# Master.net
KiCad netlist of a schematic drawn in Altium Designer
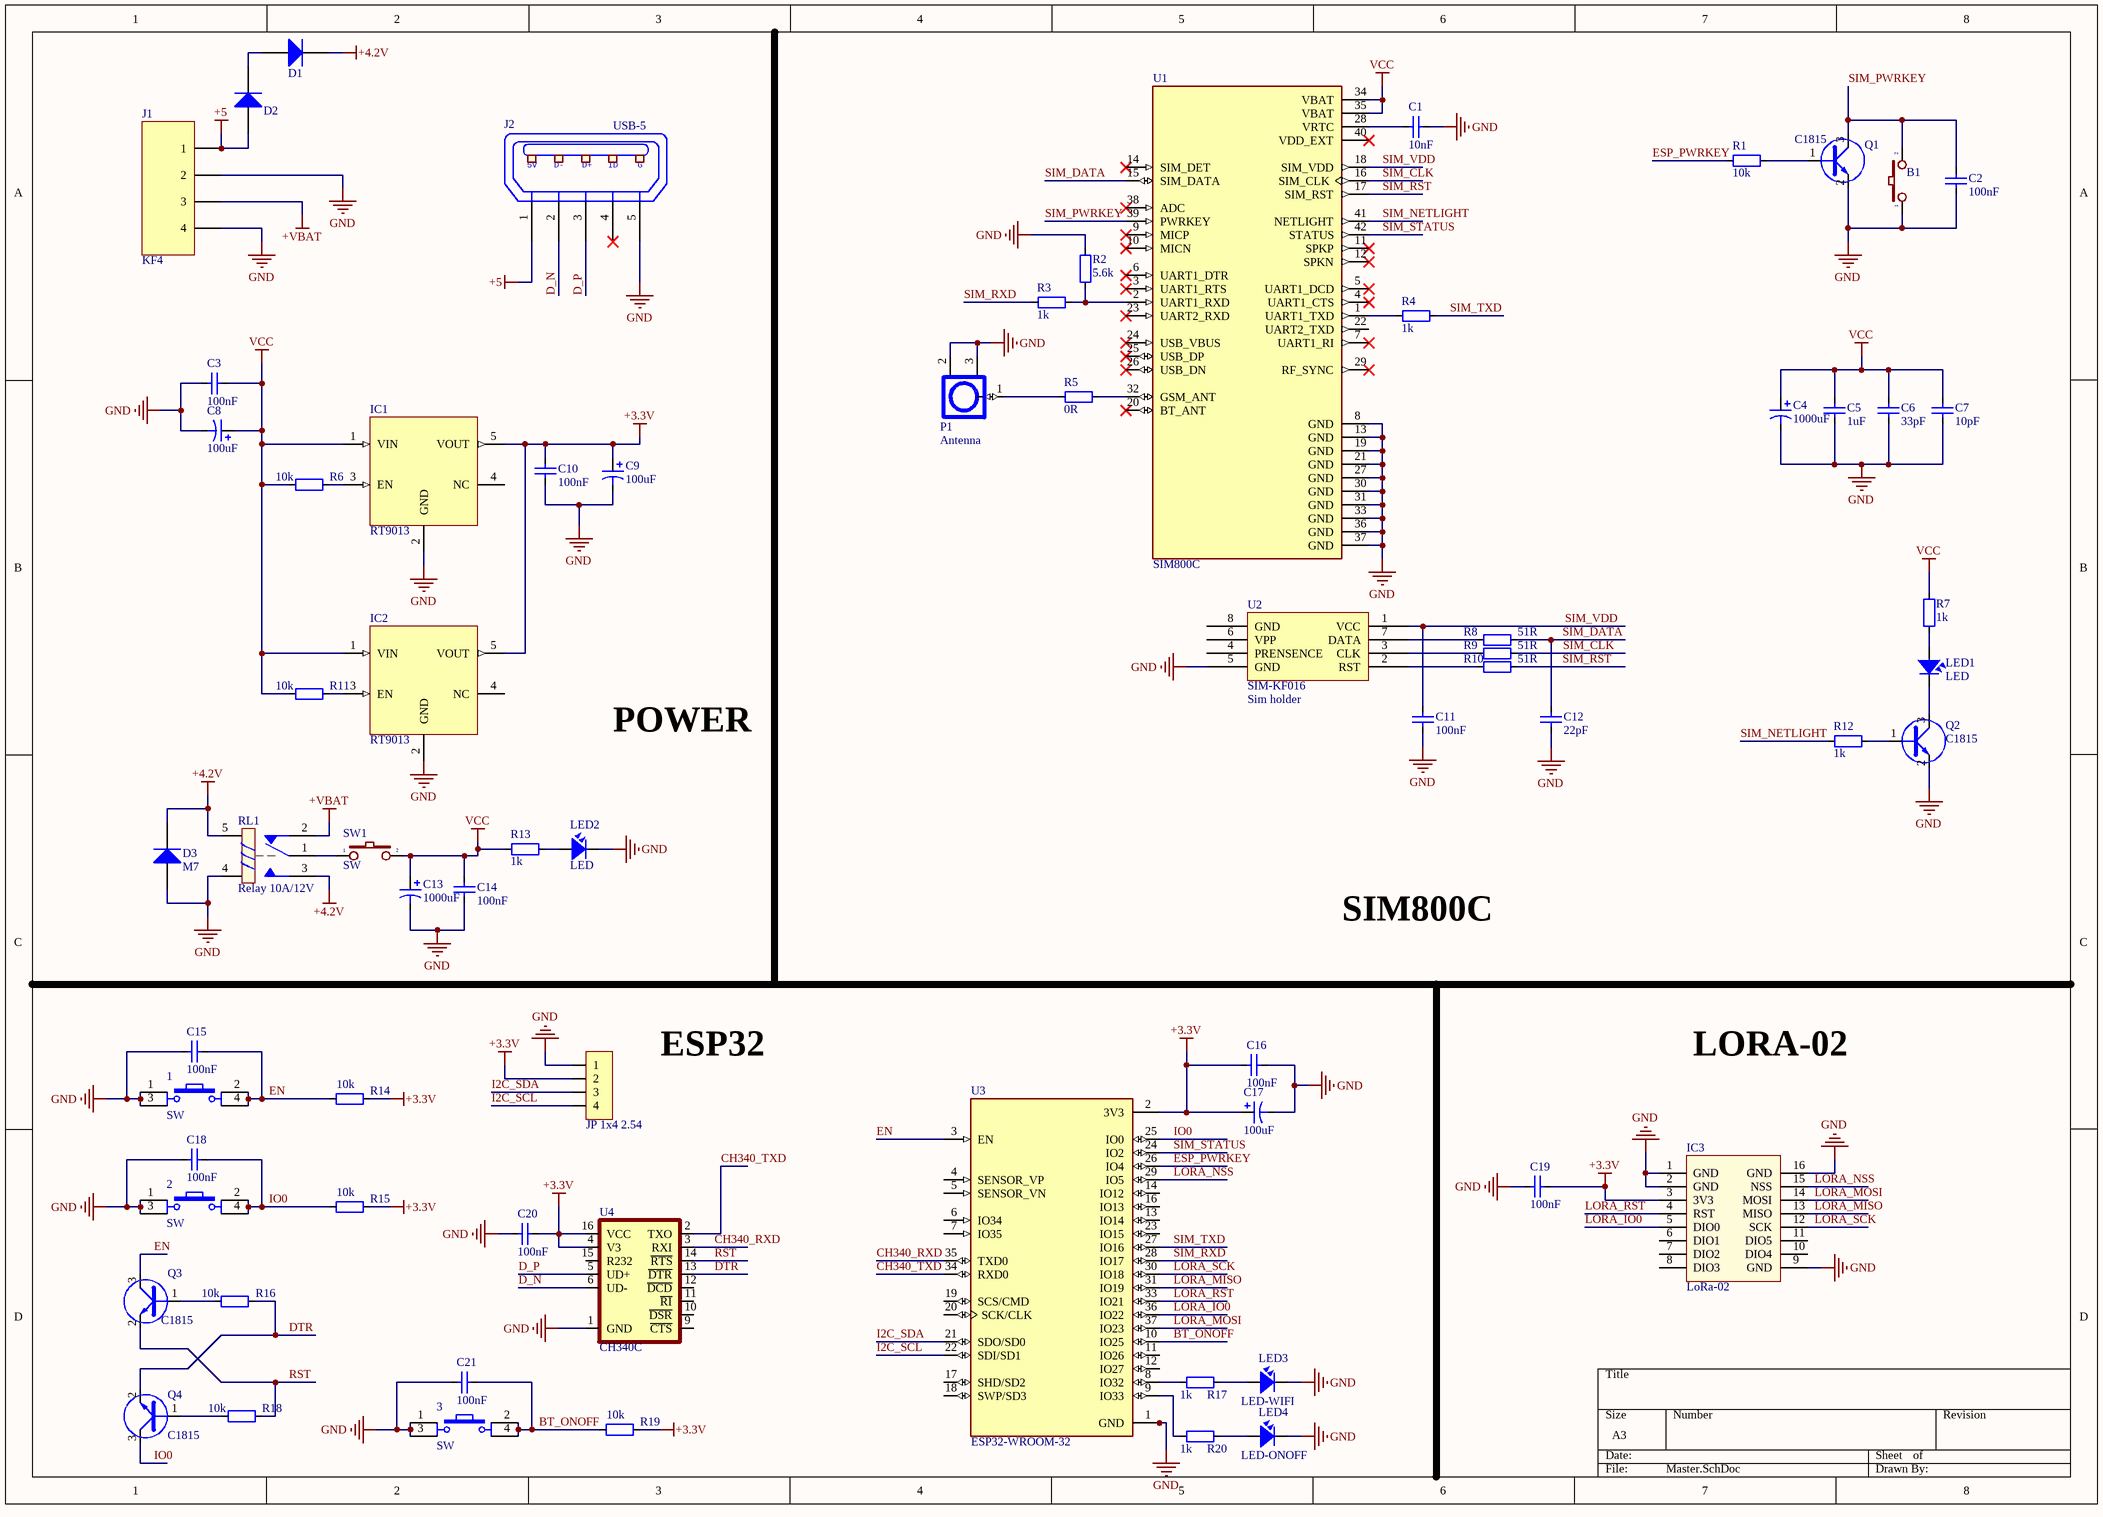
[diagram p0: Master.SchDoc]

(export (version "E")
  (design (tool "Eeschema 10.0.6"))
  (components
    (comp (ref "1")
      (value "SW")
      (footprint "SW4")
      (description "Switch button 4 pin")
      (libsource (lib "My Library") (part "SW4"))
    )
    (comp (ref "2")
      (value "SW")
      (footprint "SW4")
      (description "Switch button 4 pin")
      (libsource (lib "My Library") (part "SW4"))
    )
    (comp (ref "3")
      (value "SW")
      (footprint "SW4")
      (description "Switch button 4 pin")
      (libsource (lib "My Library") (part "SW4"))
    )
    (comp (ref "B1")
      (value "Button 3x4x2.5")
      (footprint "Button 3x4x2.5")
      (libsource (lib "My Library") (part "Button 3x4x2.5"))
    )
    (comp (ref "C1")
      (value "10nF")
      (footprint "CAP_0805")
      (description "Capacitor")
      (fields (field (name "PUBLISHER") "Altium Limited"))
      (libsource (lib "My Library") (part "CapSMD"))
    )
    (comp (ref "C2")
      (value "100nF")
      (footprint "CAP_0805")
      (description "Capacitor")
      (fields (field (name "PUBLISHER") "Altium Limited"))
      (libsource (lib "My Library") (part "CapSMD"))
    )
    (comp (ref "C3")
      (value "100nF")
      (footprint "CAP_0805")
      (description "Capacitor")
      (fields (field (name "PUBLISHER") "Altium Limited"))
      (libsource (lib "My Library") (part "CapSMD"))
    )
    (comp (ref "C4")
      (value "1000uF")
      (footprint "C8mm")
      (description "1000uF 16V 8x16mm")
      (fields (field (name "PUBLISHER") "Altium Limited"))
      (libsource (lib "My Library") (part "Cap Pol"))
    )
    (comp (ref "C5")
      (value "1uF")
      (footprint "CAP_0805")
      (description "Capacitor")
      (fields (field (name "PUBLISHER") "Altium Limited"))
      (libsource (lib "My Library") (part "CapSMD"))
    )
    (comp (ref "C6")
      (value "33pF")
      (footprint "CAP_0805")
      (description "Capacitor")
      (fields (field (name "PUBLISHER") "Altium Limited"))
      (libsource (lib "My Library") (part "CapSMD"))
    )
    (comp (ref "C7")
      (value "10pF")
      (footprint "CAP_0805")
      (description "Capacitor")
      (fields (field (name "PUBLISHER") "Altium Limited"))
      (libsource (lib "My Library") (part "CapSMD"))
    )
    (comp (ref "C8")
      (value "100uF")
      (footprint "C5mm")
      (description "100uF 16V")
      (fields (field (name "PUBLISHER") "Altium Limited"))
      (libsource (lib "My Library") (part "Cap Pol"))
    )
    (comp (ref "C9")
      (value "100uF")
      (footprint "C5mm")
      (description "100uF 16V")
      (fields (field (name "PUBLISHER") "Altium Limited"))
      (libsource (lib "My Library") (part "Cap Pol"))
    )
    (comp (ref "C10")
      (value "100nF")
      (footprint "CAP_0805")
      (description "Capacitor")
      (fields (field (name "PUBLISHER") "Altium Limited"))
      (libsource (lib "My Library") (part "CapSMD"))
    )
    (comp (ref "C11")
      (value "100nF")
      (footprint "CAP_0805")
      (description "Capacitor")
      (fields (field (name "PUBLISHER") "Altium Limited"))
      (libsource (lib "My Library") (part "CapSMD"))
    )
    (comp (ref "C12")
      (value "22pF")
      (footprint "CAP_0805")
      (description "Capacitor")
      (fields (field (name "PUBLISHER") "Altium Limited"))
      (libsource (lib "My Library") (part "CapSMD"))
    )
    (comp (ref "C13")
      (value "1000uF")
      (footprint "C8mm")
      (description "1000uF 16V 8x16mm")
      (fields (field (name "PUBLISHER") "Altium Limited"))
      (libsource (lib "My Library") (part "Cap Pol"))
    )
    (comp (ref "C14")
      (value "100nF")
      (footprint "CAP_0805")
      (description "Capacitor")
      (fields (field (name "PUBLISHER") "Altium Limited"))
      (libsource (lib "My Library") (part "CapSMD"))
    )
    (comp (ref "C15")
      (value "100nF")
      (footprint "CAP_0805")
      (description "Capacitor")
      (fields (field (name "PUBLISHER") "Altium Limited"))
      (libsource (lib "My Library") (part "CapSMD"))
    )
    (comp (ref "C16")
      (value "100nF")
      (footprint "CAP_0805")
      (description "Capacitor")
      (fields (field (name "PUBLISHER") "Altium Limited"))
      (libsource (lib "My Library") (part "CapSMD"))
    )
    (comp (ref "C17")
      (value "100uF")
      (footprint "C5mm")
      (description "100uF 16V")
      (fields (field (name "PUBLISHER") "Altium Limited"))
      (libsource (lib "My Library") (part "Cap Pol"))
    )
    (comp (ref "C18")
      (value "100nF")
      (footprint "CAP_0805")
      (description "Capacitor")
      (fields (field (name "PUBLISHER") "Altium Limited"))
      (libsource (lib "My Library") (part "CapSMD"))
    )
    (comp (ref "C19")
      (value "100nF")
      (footprint "CAP_0805")
      (description "Capacitor")
      (fields (field (name "PUBLISHER") "Altium Limited"))
      (libsource (lib "My Library") (part "CapSMD"))
    )
    (comp (ref "C20")
      (value "100nF")
      (footprint "CAP_0805")
      (description "Capacitor")
      (fields (field (name "PUBLISHER") "Altium Limited"))
      (libsource (lib "My Library") (part "CapSMD"))
    )
    (comp (ref "C21")
      (value "100nF")
      (footprint "CAP_0805")
      (description "Capacitor")
      (fields (field (name "PUBLISHER") "Altium Limited"))
      (libsource (lib "My Library") (part "CapSMD"))
    )
    (comp (ref "D1")
      (value "SS34 Diode 3A 40V")
      (footprint "DIODE SMA")
      (description "Dán")
      (libsource (lib "Altium_Lib_by_KhueNguyenCreator") (part "Diode M7 ( 4007 )"))
    )
    (comp (ref "D2")
      (value "SS34 Diode 3A 40V")
      (footprint "DIODE SMA")
      (description "Dán")
      (libsource (lib "Altium_Lib_by_KhueNguyenCreator") (part "Diode M7 ( 4007 )"))
    )
    (comp (ref "D3")
      (value "M7")
      (footprint "DIODE SMA")
      (description "Dán")
      (libsource (lib "Altium_Lib_by_KhueNguyenCreator") (part "Diode M7 ( 4007 )"))
    )
    (comp (ref "IC1")
      (value "RT9013")
      (footprint "SOT23-5")
      (description "RT9013-33GB IC REG LINEAR 3.3V 500mA SOT23-5")
      (libsource (lib "My Library") (part "RT9013"))
    )
    (comp (ref "IC2")
      (value "RT9013")
      (footprint "SOT23-5")
      (description "RT9013-33GB IC REG LINEAR 3.3V 500mA SOT23-5")
      (libsource (lib "My Library") (part "RT9013"))
    )
    (comp (ref "IC3") (value "LoRa-02") (footprint "LoRa-02") (libsource (lib "My Library") (part "LoRa-02")))
    (comp (ref "J1")
      (value "KF4")
      (footprint "KF4-5.08")
      (fields
        (field (name "MANUFACTURER") "Würth Elektronik eiSos GmbH")
        (field (name "PARTNO") "691133710004")
        (field (name "CREATED BY") "Baojun Chen")
      )
      (libsource (lib "My Library") (part "KF4"))
    )
    (comp (ref "J2")
      (value "USB-5")
      (footprint "USB-M1")
      (fields
        (field (name "MANUFACTURER") "FCI")
        (field (name "MANUFACTURER PART NUMBER") "10118193-0001LF")
        (field (name ".CREATOR") "MM")
        (field (name ".CHECKED PCB") "RF")
        (field (name ".CHECKED SCH") "MM")
      )
      (libsource (lib "My Library") (part "USB-5"))
    )
    (comp (ref "JP1")
      (value "JP 1x4 2.54")
      (footprint "JP 1x4 DT")
      (description "Cắm")
      (libsource (lib "Altium_Lib_by_KhueNguyenCreator") (part "JP 1x4 2.54 Duc Thang"))
    )
    (comp (ref "LED1")
      (value "LED")
      (footprint "LED-0805-Red")
      (description "LED Single colour Green and Red")
      (libsource (lib "My Library") (part "LED"))
    )
    (comp (ref "LED2")
      (value "LED")
      (footprint "LED-0805-Red")
      (description "LED Single colour Green and Red")
      (libsource (lib "My Library") (part "LED"))
    )
    (comp (ref "LED3")
      (value "LED-WIFI")
      (footprint "LED-0805-Red")
      (description "LED Single colour Green and Red")
      (libsource (lib "My Library") (part "LED"))
    )
    (comp (ref "LED4")
      (value "LED-ONOFF")
      (footprint "LED-0805-Red")
      (description "LED Single colour Green and Red")
      (libsource (lib "My Library") (part "LED"))
    )
    (comp (ref "P1")
      (value "Antenna")
      (footprint "IPXS")
      (description "Antenna GSM GPS")
      (libsource (lib "My Library") (part "IPXSx66"))
    )
    (comp (ref "Q1")
      (value "C1815")
      (footprint "SOT23D")
      (description "NPN 600mW, ECB")
      (libsource (lib "My Library") (part "2SC1815"))
    )
    (comp (ref "Q2")
      (value "C1815")
      (footprint "SOT23D")
      (description "NPN 600mW, ECB")
      (libsource (lib "My Library") (part "2SC1815"))
    )
    (comp (ref "Q3")
      (value "C1815")
      (footprint "SOT23D")
      (description "NPN 600mW, ECB")
      (libsource (lib "") (part "2SC1815_1"))
    )
    (comp (ref "Q4")
      (value "C1815")
      (footprint "SOT23D")
      (description "NPN 600mW, ECB")
      (libsource (lib "My Library") (part "2SC1815"))
    )
    (comp (ref "R1")
      (value "10k")
      (footprint "RES-SMD-0805")
      (description "Resistor")
      (fields
        (field (name "MANUFACTURER") "Generic Components")
        (field (name "PUBLISHER") "Altium Hobart Technology Centre")
      )
      (libsource (lib "My Library") (part "Resistor - SMD"))
    )
    (comp (ref "R2")
      (value "5.6k")
      (footprint "RES-SMD-0805")
      (description "Resistor")
      (fields
        (field (name "MANUFACTURER") "Generic Components")
        (field (name "PUBLISHER") "Altium Hobart Technology Centre")
      )
      (libsource (lib "My Library") (part "Resistor - SMD"))
    )
    (comp (ref "R3")
      (value "1k")
      (footprint "RES-SMD-0805")
      (description "Resistor")
      (fields
        (field (name "MANUFACTURER") "Generic Components")
        (field (name "PUBLISHER") "Altium Hobart Technology Centre")
      )
      (libsource (lib "My Library") (part "Resistor - SMD"))
    )
    (comp (ref "R4")
      (value "1k")
      (footprint "RES-SMD-0805")
      (description "Resistor")
      (fields
        (field (name "MANUFACTURER") "Generic Components")
        (field (name "PUBLISHER") "Altium Hobart Technology Centre")
      )
      (libsource (lib "My Library") (part "Resistor - SMD"))
    )
    (comp (ref "R5")
      (value "0R")
      (footprint "RES-SMD-0805")
      (description "Resistor")
      (fields
        (field (name "MANUFACTURER") "Generic Components")
        (field (name "PUBLISHER") "Altium Hobart Technology Centre")
      )
      (libsource (lib "My Library") (part "Resistor - SMD"))
    )
    (comp (ref "R6")
      (value "10k")
      (footprint "RES-SMD-0805")
      (description "Resistor")
      (fields
        (field (name "MANUFACTURER") "Generic Components")
        (field (name "PUBLISHER") "Altium Hobart Technology Centre")
      )
      (libsource (lib "My Library") (part "Resistor - SMD"))
    )
    (comp (ref "R7")
      (value "1k")
      (footprint "RES-SMD-0805")
      (description "Resistor")
      (fields
        (field (name "MANUFACTURER") "Generic Components")
        (field (name "PUBLISHER") "Altium Hobart Technology Centre")
      )
      (libsource (lib "My Library") (part "Resistor - SMD"))
    )
    (comp (ref "R8")
      (value "51R")
      (footprint "RES-SMD-0805")
      (description "Resistor")
      (fields
        (field (name "MANUFACTURER") "Generic Components")
        (field (name "PUBLISHER") "Altium Hobart Technology Centre")
      )
      (libsource (lib "My Library") (part "Resistor - SMD"))
    )
    (comp (ref "R9")
      (value "51R")
      (footprint "RES-SMD-0805")
      (description "Resistor")
      (fields
        (field (name "MANUFACTURER") "Generic Components")
        (field (name "PUBLISHER") "Altium Hobart Technology Centre")
      )
      (libsource (lib "My Library") (part "Resistor - SMD"))
    )
    (comp (ref "R10")
      (value "51R")
      (footprint "RES-SMD-0805")
      (description "Resistor")
      (fields
        (field (name "MANUFACTURER") "Generic Components")
        (field (name "PUBLISHER") "Altium Hobart Technology Centre")
      )
      (libsource (lib "My Library") (part "Resistor - SMD"))
    )
    (comp (ref "R11")
      (value "10k")
      (footprint "RES-SMD-0805")
      (description "Resistor")
      (fields
        (field (name "MANUFACTURER") "Generic Components")
        (field (name "PUBLISHER") "Altium Hobart Technology Centre")
      )
      (libsource (lib "My Library") (part "Resistor - SMD"))
    )
    (comp (ref "R12")
      (value "1k")
      (footprint "RES-SMD-0805")
      (description "Resistor")
      (fields
        (field (name "MANUFACTURER") "Generic Components")
        (field (name "PUBLISHER") "Altium Hobart Technology Centre")
      )
      (libsource (lib "My Library") (part "Resistor - SMD"))
    )
    (comp (ref "R13")
      (value "1k")
      (footprint "RES-SMD-0805")
      (description "Resistor")
      (fields
        (field (name "MANUFACTURER") "Generic Components")
        (field (name "PUBLISHER") "Altium Hobart Technology Centre")
      )
      (libsource (lib "My Library") (part "Resistor - SMD"))
    )
    (comp (ref "R14")
      (value "10k")
      (footprint "RES-SMD-0805")
      (description "Resistor")
      (fields
        (field (name "MANUFACTURER") "Generic Components")
        (field (name "PUBLISHER") "Altium Hobart Technology Centre")
      )
      (libsource (lib "My Library") (part "Resistor - SMD"))
    )
    (comp (ref "R15")
      (value "10k")
      (footprint "RES-SMD-0805")
      (description "Resistor")
      (fields
        (field (name "MANUFACTURER") "Generic Components")
        (field (name "PUBLISHER") "Altium Hobart Technology Centre")
      )
      (libsource (lib "My Library") (part "Resistor - SMD"))
    )
    (comp (ref "R16")
      (value "10k")
      (footprint "RES-SMD-0805")
      (description "Resistor")
      (fields
        (field (name "MANUFACTURER") "Generic Components")
        (field (name "PUBLISHER") "Altium Hobart Technology Centre")
      )
      (libsource (lib "My Library") (part "Resistor - SMD"))
    )
    (comp (ref "R17")
      (value "1k")
      (footprint "RES-SMD-0805")
      (description "Resistor")
      (fields
        (field (name "MANUFACTURER") "Generic Components")
        (field (name "PUBLISHER") "Altium Hobart Technology Centre")
      )
      (libsource (lib "My Library") (part "Resistor - SMD"))
    )
    (comp (ref "R18")
      (value "10k")
      (footprint "RES-SMD-0805")
      (description "Resistor")
      (fields
        (field (name "MANUFACTURER") "Generic Components")
        (field (name "PUBLISHER") "Altium Hobart Technology Centre")
      )
      (libsource (lib "My Library") (part "Resistor - SMD"))
    )
    (comp (ref "R19")
      (value "10k")
      (footprint "RES-SMD-0805")
      (description "Resistor")
      (fields
        (field (name "MANUFACTURER") "Generic Components")
        (field (name "PUBLISHER") "Altium Hobart Technology Centre")
      )
      (libsource (lib "My Library") (part "Resistor - SMD"))
    )
    (comp (ref "R20")
      (value "1k")
      (footprint "RES-SMD-0805")
      (description "Resistor")
      (fields
        (field (name "MANUFACTURER") "Generic Components")
        (field (name "PUBLISHER") "Altium Hobart Technology Centre")
      )
      (libsource (lib "My Library") (part "Resistor - SMD"))
    )
    (comp (ref "RL1")
      (value "Relay 10A/12V")
      (footprint "RELAY 5")
      (description "Relay SPDT,10A - 12VDC 5 Pin")
      (libsource (lib "My Library") (part "Relay 5"))
    )
    (comp (ref "SW1")
      (value "SW")
      (footprint "SW2")
      (description "Switch button 2 pin")
      (libsource (lib "My Library") (part "SW2"))
    )
    (comp (ref "U1") (value "SIM800C") (footprint "SIM800C") (libsource (lib "My Library") (part "SIM800C")))
    (comp (ref "U2")
      (value "SIM-KF016")
      (footprint "Sim Socket")
      (description "SIM Card Holder KF-016")
      (fields (field (name "ALTIUM_VALUE") "Sim holder"))
      (libsource (lib "My Library") (part "Sim holder"))
    )
    (comp (ref "U3")
      (value "ESP32-WROOM-32")
      (footprint "MODULE_ESP32-WROOM-32")
      (description "Bluetooth, WiFi Transceiver Module 2.4GHz ~ 2.5GHz Surface Mount")
      (fields (field (name "MF") "Espressif Systems") (field (name "DIGI-KEY_PART_NUMBER") "1904-1010-1-ND"))
      (libsource (lib "My Library") (part "ESP32-WROOM-32"))
    )
    (comp (ref "U4")
      (value "CH340C")
      (footprint "SO016")
      (description "USB to serial chip CH340")
      (fields (field (name "MF") "WCH"))
      (libsource (lib "My Library") (part "CH340C"))
    )
  )
  (nets
    (net (code "1") (name "+3.3V") (class "Default")
      (node (ref "C10") (pin "1") (pinfunction "1_1") (pintype "passive"))
      (node (ref "C16") (pin "1") (pinfunction "1_1") (pintype "passive"))
      (node (ref "C17") (pin "1") (pinfunction "1_1") (pintype "passive"))
      (node (ref "C19") (pin "1") (pinfunction "1_1") (pintype "passive"))
      (node (ref "C20") (pin "2") (pinfunction "2_2") (pintype "passive"))
      (node (ref "C9") (pin "1") (pinfunction "1_1") (pintype "passive"))
      (node (ref "IC1") (pin "5") (pinfunction "VOUT_5") (pintype "output"))
      (node (ref "IC2") (pin "5") (pinfunction "VOUT_5") (pintype "output"))
      (node (ref "IC3") (pin "3") (pinfunction "3V3_3") (pintype "passive"))
      (node (ref "JP1") (pin "2") (pinfunction "2_2") (pintype "passive"))
      (node (ref "R14") (pin "1") (pinfunction "1_1") (pintype "passive"))
      (node (ref "R15") (pin "1") (pinfunction "1_1") (pintype "passive"))
      (node (ref "R19") (pin "1") (pinfunction "1_1") (pintype "passive"))
      (node (ref "U3") (pin "2") (pinfunction "3V3_2") (pintype "power_in"))
      (node (ref "U4") (pin "16") (pinfunction "VCC_16") (pintype "bidirectional"))
      (node (ref "U4") (pin "4") (pinfunction "V3_4") (pintype "bidirectional"))
    )
    (net (code "2") (name "+4.2V") (class "Default")
      (node (ref "D1") (pin "2") (pinfunction "K_2") (pintype "passive"))
      (node (ref "D3") (pin "2") (pinfunction "K_2") (pintype "passive"))
      (node (ref "RL1") (pin "3") (pinfunction "3_3") (pintype "passive"))
      (node (ref "RL1") (pin "5") (pinfunction "5_5") (pintype "passive"))
    )
    (net (code "3") (name "+5") (class "Default")
      (node (ref "D2") (pin "1") (pinfunction "A_1") (pintype "passive"))
      (node (ref "J1") (pin "1") (pinfunction "1_1") (pintype "passive"))
      (node (ref "J2") (pin "1") (pinfunction "P1_1") (pintype "passive"))
    )
    (net (code "4") (name "+VBAT") (class "Default")
      (node (ref "J1") (pin "3") (pinfunction "3_3") (pintype "passive"))
      (node (ref "RL1") (pin "2") (pinfunction "2_2") (pintype "passive"))
    )
    (net (code "6") (name "/BT_ONOFF") (class "Default")
      (node (ref "3") (pin "2") (pintype "passive"))
      (node (ref "3") (pin "4") (pintype "passive"))
      (node (ref "C21") (pin "2") (pinfunction "2_2") (pintype "passive"))
      (node (ref "R19") (pin "2") (pinfunction "2_2") (pintype "passive"))
      (node (ref "U3") (pin "10") (pinfunction "IO25_10") (pintype "bidirectional"))
    )
    (net (code "7") (name "/CH340_RXD") (class "Default")
      (node (ref "U3") (pin "35") (pinfunction "TXD0_35") (pintype "bidirectional"))
      (node (ref "U4") (pin "3") (pinfunction "RXI_3") (pintype "bidirectional"))
    )
    (net (code "8") (name "/CH340_TXD") (class "Default")
      (node (ref "U3") (pin "34") (pinfunction "RXD0_34") (pintype "bidirectional"))
      (node (ref "U4") (pin "2") (pinfunction "TXO_2") (pintype "bidirectional"))
    )
    (net (code "9") (name "/DTR") (class "Default")
      (node (ref "Q4") (pin "2") (pinfunction "E_2") (pintype "passive"))
      (node (ref "R16") (pin "1") (pinfunction "1_1") (pintype "passive"))
      (node (ref "U4") (pin "13") (pinfunction "~{DTR}_13") (pintype "bidirectional"))
    )
    (net (code "10") (name "/D_N") (class "Default")
      (node (ref "J2") (pin "2") (pinfunction "P2_2") (pintype "passive"))
      (node (ref "U4") (pin "6") (pinfunction "UD-_6") (pintype "bidirectional"))
    )
    (net (code "11") (name "/D_P") (class "Default")
      (node (ref "J2") (pin "3") (pinfunction "P3_3") (pintype "passive"))
      (node (ref "U4") (pin "5") (pinfunction "UD+_5") (pintype "bidirectional"))
    )
    (net (code "12") (name "/EN") (class "Default")
      (node (ref "1") (pin "2") (pintype "passive"))
      (node (ref "1") (pin "4") (pintype "passive"))
      (node (ref "C15") (pin "2") (pinfunction "2_2") (pintype "passive"))
      (node (ref "Q3") (pin "3") (pinfunction "C_3") (pintype "passive"))
      (node (ref "R14") (pin "2") (pinfunction "2_2") (pintype "passive"))
      (node (ref "U3") (pin "3") (pinfunction "EN_3") (pintype "input"))
    )
    (net (code "13") (name "/ESP_PWRKEY") (class "Default")
      (node (ref "R1") (pin "1") (pinfunction "1_1") (pintype "passive"))
      (node (ref "U3") (pin "26") (pinfunction "IO4_26") (pintype "bidirectional"))
    )
    (net (code "14") (name "/I2C_SCL") (class "Default")
      (node (ref "JP1") (pin "4") (pinfunction "4_4") (pintype "passive"))
      (node (ref "U3") (pin "22") (pinfunction "SDI/SD1_22") (pintype "bidirectional"))
    )
    (net (code "15") (name "/I2C_SDA") (class "Default")
      (node (ref "JP1") (pin "3") (pinfunction "3_3") (pintype "passive"))
      (node (ref "U3") (pin "21") (pinfunction "SDO/SD0_21") (pintype "bidirectional"))
    )
    (net (code "16") (name "/IO0") (class "Default")
      (node (ref "2") (pin "2") (pintype "passive"))
      (node (ref "2") (pin "4") (pintype "passive"))
      (node (ref "C18") (pin "2") (pinfunction "2_2") (pintype "passive"))
      (node (ref "Q4") (pin "3") (pinfunction "C_3") (pintype "passive"))
      (node (ref "R15") (pin "2") (pinfunction "2_2") (pintype "passive"))
      (node (ref "U3") (pin "25") (pinfunction "IO0_25") (pintype "bidirectional"))
    )
    (net (code "17") (name "/LORA_IO0") (class "Default")
      (node (ref "IC3") (pin "5") (pinfunction "DIO0_5") (pintype "passive"))
      (node (ref "U3") (pin "36") (pinfunction "IO22_36") (pintype "bidirectional"))
    )
    (net (code "18") (name "/LORA_MISO") (class "Default")
      (node (ref "IC3") (pin "13") (pinfunction "MISO_13") (pintype "passive"))
      (node (ref "U3") (pin "31") (pinfunction "IO19_31") (pintype "bidirectional"))
    )
    (net (code "19") (name "/LORA_MOSI") (class "Default")
      (node (ref "IC3") (pin "14") (pinfunction "MOSI_14") (pintype "passive"))
      (node (ref "U3") (pin "37") (pinfunction "IO23_37") (pintype "bidirectional"))
    )
    (net (code "20") (name "/LORA_NSS") (class "Default")
      (node (ref "IC3") (pin "15") (pinfunction "NSS_15") (pintype "passive"))
      (node (ref "U3") (pin "29") (pinfunction "IO5_29") (pintype "bidirectional"))
    )
    (net (code "21") (name "/LORA_RST") (class "Default")
      (node (ref "IC3") (pin "4") (pinfunction "RST_4") (pintype "passive"))
      (node (ref "U3") (pin "33") (pinfunction "IO21_33") (pintype "bidirectional"))
    )
    (net (code "22") (name "/LORA_SCK") (class "Default")
      (node (ref "IC3") (pin "12") (pinfunction "SCK_12") (pintype "passive"))
      (node (ref "U3") (pin "30") (pinfunction "IO18_30") (pintype "bidirectional"))
    )
    (net (code "23") (name "/RST") (class "Default")
      (node (ref "Q3") (pin "2") (pinfunction "E_2") (pintype "passive"))
      (node (ref "R18") (pin "1") (pinfunction "1_1") (pintype "passive"))
      (node (ref "U4") (pin "14") (pinfunction "~{RTS}_14") (pintype "bidirectional"))
    )
    (net (code "24") (name "/SIM_CLK") (class "Default")
      (node (ref "R9") (pin "2") (pinfunction "2_2") (pintype "passive"))
      (node (ref "U1") (pin "16") (pinfunction "SIM_CLK_16") (pintype "output"))
    )
    (net (code "25") (name "/SIM_DATA") (class "Default")
      (node (ref "C12") (pin "2") (pinfunction "2_2") (pintype "passive"))
      (node (ref "R8") (pin "2") (pinfunction "2_2") (pintype "passive"))
      (node (ref "U1") (pin "15") (pinfunction "SIM_DATA_15") (pintype "bidirectional"))
    )
    (net (code "26") (name "/SIM_NETLIGHT") (class "Default")
      (node (ref "R12") (pin "1") (pinfunction "1_1") (pintype "passive"))
      (node (ref "U1") (pin "41") (pinfunction "NETLIGHT_41") (pintype "output"))
    )
    (net (code "27") (name "/SIM_PWRKEY") (class "Default")
      (node (ref "B1") (pin "2") (pinfunction "2_2") (pintype "passive"))
      (node (ref "C2") (pin "2") (pinfunction "2_2") (pintype "passive"))
      (node (ref "Q1") (pin "3") (pinfunction "C_3") (pintype "passive"))
      (node (ref "U1") (pin "39") (pinfunction "PWRKEY_39") (pintype "input"))
    )
    (net (code "28") (name "/SIM_RST") (class "Default")
      (node (ref "R10") (pin "2") (pinfunction "2_2") (pintype "passive"))
      (node (ref "U1") (pin "17") (pinfunction "SIM_RST_17") (pintype "output"))
    )
    (net (code "29") (name "/SIM_RXD") (class "Default")
      (node (ref "R3") (pin "1") (pinfunction "1_1") (pintype "passive"))
      (node (ref "U3") (pin "28") (pinfunction "IO17_28") (pintype "bidirectional"))
    )
    (net (code "30") (name "/SIM_STATUS") (class "Default")
      (node (ref "U1") (pin "42") (pinfunction "STATUS_42") (pintype "output"))
      (node (ref "U3") (pin "24") (pinfunction "IO2_24") (pintype "bidirectional"))
    )
    (net (code "31") (name "/SIM_TXD") (class "Default")
      (node (ref "R4") (pin "1") (pinfunction "1_1") (pintype "passive"))
      (node (ref "U3") (pin "27") (pinfunction "IO16_27") (pintype "bidirectional"))
    )
    (net (code "32") (name "/SIM_VDD") (class "Default")
      (node (ref "C11") (pin "1") (pinfunction "1_1") (pintype "passive"))
      (node (ref "U1") (pin "18") (pinfunction "SIM_VDD_18") (pintype "output"))
      (node (ref "U2") (pin "1") (pinfunction "VCC_1") (pintype "passive"))
    )
    (net (code "33") (name "GND") (class "Default")
      (node (ref "1") (pin "1") (pintype "passive"))
      (node (ref "1") (pin "3") (pintype "passive"))
      (node (ref "2") (pin "1") (pintype "passive"))
      (node (ref "2") (pin "3") (pintype "passive"))
      (node (ref "3") (pin "1") (pintype "passive"))
      (node (ref "3") (pin "3") (pintype "passive"))
      (node (ref "B1") (pin "1") (pinfunction "1_1") (pintype "passive"))
      (node (ref "C1") (pin "2") (pinfunction "2_2") (pintype "passive"))
      (node (ref "C10") (pin "2") (pinfunction "2_2") (pintype "passive"))
      (node (ref "C11") (pin "2") (pinfunction "2_2") (pintype "passive"))
      (node (ref "C12") (pin "1") (pinfunction "1_1") (pintype "passive"))
      (node (ref "C13") (pin "2") (pinfunction "2_2") (pintype "passive"))
      (node (ref "C14") (pin "2") (pinfunction "2_2") (pintype "passive"))
      (node (ref "C15") (pin "1") (pinfunction "1_1") (pintype "passive"))
      (node (ref "C16") (pin "2") (pinfunction "2_2") (pintype "passive"))
      (node (ref "C17") (pin "2") (pinfunction "2_2") (pintype "passive"))
      (node (ref "C18") (pin "1") (pinfunction "1_1") (pintype "passive"))
      (node (ref "C19") (pin "2") (pinfunction "2_2") (pintype "passive"))
      (node (ref "C2") (pin "1") (pinfunction "1_1") (pintype "passive"))
      (node (ref "C20") (pin "1") (pinfunction "1_1") (pintype "passive"))
      (node (ref "C21") (pin "1") (pinfunction "1_1") (pintype "passive"))
      (node (ref "C3") (pin "2") (pinfunction "2_2") (pintype "passive"))
      (node (ref "C4") (pin "2") (pinfunction "2_2") (pintype "passive"))
      (node (ref "C5") (pin "2") (pinfunction "2_2") (pintype "passive"))
      (node (ref "C6") (pin "2") (pinfunction "2_2") (pintype "passive"))
      (node (ref "C7") (pin "2") (pinfunction "2_2") (pintype "passive"))
      (node (ref "C8") (pin "2") (pinfunction "2_2") (pintype "passive"))
      (node (ref "C9") (pin "2") (pinfunction "2_2") (pintype "passive"))
      (node (ref "D3") (pin "1") (pinfunction "A_1") (pintype "passive"))
      (node (ref "IC1") (pin "2") (pinfunction "GND_2") (pintype "passive"))
      (node (ref "IC2") (pin "2") (pinfunction "GND_2") (pintype "passive"))
      (node (ref "IC3") (pin "1") (pinfunction "GND_1") (pintype "passive"))
      (node (ref "IC3") (pin "16") (pinfunction "GND_16") (pintype "passive"))
      (node (ref "IC3") (pin "2") (pinfunction "GND_2") (pintype "passive"))
      (node (ref "IC3") (pin "9") (pinfunction "GND_9") (pintype "passive"))
      (node (ref "J1") (pin "2") (pinfunction "2_2") (pintype "passive"))
      (node (ref "J1") (pin "4") (pinfunction "4_4") (pintype "passive"))
      (node (ref "J2") (pin "5") (pinfunction "P5_5") (pintype "passive"))
      (node (ref "JP1") (pin "1") (pinfunction "1_1") (pintype "passive"))
      (node (ref "LED2") (pin "2") (pinfunction "2_2") (pintype "passive"))
      (node (ref "LED3") (pin "2") (pinfunction "2_2") (pintype "passive"))
      (node (ref "LED4") (pin "2") (pinfunction "2_2") (pintype "passive"))
      (node (ref "P1") (pin "2") (pintype "passive"))
      (node (ref "P1") (pin "3") (pintype "passive"))
      (node (ref "Q1") (pin "2") (pinfunction "E_2") (pintype "passive"))
      (node (ref "Q2") (pin "2") (pinfunction "E_2") (pintype "passive"))
      (node (ref "R2") (pin "1") (pinfunction "1_1") (pintype "passive"))
      (node (ref "RL1") (pin "4") (pinfunction "4_4") (pintype "passive"))
      (node (ref "U1") (pin "13") (pinfunction "GND_13") (pintype "power_in"))
      (node (ref "U1") (pin "19") (pinfunction "GND_19") (pintype "power_in"))
      (node (ref "U1") (pin "21") (pinfunction "GND_21") (pintype "power_in"))
      (node (ref "U1") (pin "27") (pinfunction "GND_27") (pintype "power_in"))
      (node (ref "U1") (pin "30") (pinfunction "GND_30") (pintype "power_in"))
      (node (ref "U1") (pin "31") (pinfunction "GND_31") (pintype "power_in"))
      (node (ref "U1") (pin "33") (pinfunction "GND_33") (pintype "power_in"))
      (node (ref "U1") (pin "36") (pinfunction "GND_36") (pintype "power_in"))
      (node (ref "U1") (pin "37") (pinfunction "GND_37") (pintype "power_in"))
      (node (ref "U1") (pin "8") (pinfunction "GND_8") (pintype "power_in"))
      (node (ref "U2") (pin "5") (pinfunction "GND_5") (pintype "passive"))
      (node (ref "U3") (pin "1") (pinfunction "GND_1") (pintype "power_in"))
      (node (ref "U3") (pin "15") (pinfunction "GND_15") (pintype "power_in"))
      (node (ref "U3") (pin "38") (pinfunction "GND_38") (pintype "power_in"))
      (node (ref "U3") (pin "39_1") (pinfunction "GND_39_1") (pintype "power_in"))
      (node (ref "U3") (pin "39_10") (pinfunction "GND_39_10") (pintype "power_in"))
      (node (ref "U3") (pin "39_11") (pinfunction "GND_39_11") (pintype "power_in"))
      (node (ref "U3") (pin "39_12") (pinfunction "GND_39_12") (pintype "power_in"))
      (node (ref "U3") (pin "39_13") (pinfunction "GND_39_13") (pintype "power_in"))
      (node (ref "U3") (pin "39_14") (pinfunction "GND_39_14") (pintype "power_in"))
      (node (ref "U3") (pin "39_15") (pinfunction "GND_39_15") (pintype "power_in"))
      (node (ref "U3") (pin "39_16") (pinfunction "GND_39_16") (pintype "power_in"))
      (node (ref "U3") (pin "39_17") (pinfunction "GND_39_17") (pintype "power_in"))
      (node (ref "U3") (pin "39_18") (pinfunction "GND_39_18") (pintype "power_in"))
      (node (ref "U3") (pin "39_19") (pinfunction "GND_39_19") (pintype "power_in"))
      (node (ref "U3") (pin "39_2") (pinfunction "GND_39_2") (pintype "power_in"))
      (node (ref "U3") (pin "39_20") (pinfunction "GND_39_20") (pintype "power_in"))
      (node (ref "U3") (pin "39_21") (pinfunction "GND_39_21") (pintype "power_in"))
      (node (ref "U3") (pin "39_3") (pinfunction "GND_39_3") (pintype "power_in"))
      (node (ref "U3") (pin "39_4") (pinfunction "GND_39_4") (pintype "power_in"))
      (node (ref "U3") (pin "39_5") (pinfunction "GND_39_5") (pintype "power_in"))
      (node (ref "U3") (pin "39_6") (pinfunction "GND_39_6") (pintype "power_in"))
      (node (ref "U3") (pin "39_7") (pinfunction "GND_39_7") (pintype "power_in"))
      (node (ref "U3") (pin "39_8") (pinfunction "GND_39_8") (pintype "power_in"))
      (node (ref "U3") (pin "39_9") (pinfunction "GND_39_9") (pintype "power_in"))
      (node (ref "U4") (pin "1") (pinfunction "GND_1") (pintype "bidirectional"))
    )
    (net (code "34") (name "Net-(D1-A)") (class "Default")
      (node (ref "D1") (pin "1") (pinfunction "A_1") (pintype "passive"))
      (node (ref "D2") (pin "2") (pinfunction "K_2") (pintype "passive"))
    )
    (net (code "35") (name "Net-(IC1-EN)") (class "Default")
      (node (ref "IC1") (pin "3") (pinfunction "EN_3") (pintype "input"))
      (node (ref "R6") (pin "1") (pinfunction "1_1") (pintype "passive"))
    )
    (net (code "36") (name "Net-(IC2-EN)") (class "Default")
      (node (ref "IC2") (pin "3") (pinfunction "EN_3") (pintype "input"))
      (node (ref "R11") (pin "1") (pinfunction "1_1") (pintype "passive"))
    )
    (net (code "37") (name "Net-(LED1-Pad1)") (class "Default")
      (node (ref "LED1") (pin "1") (pinfunction "1_1") (pintype "passive"))
      (node (ref "R7") (pin "1") (pinfunction "1_1") (pintype "passive"))
    )
    (net (code "38") (name "Net-(LED2-Pad1)") (class "Default")
      (node (ref "LED2") (pin "1") (pinfunction "1_1") (pintype "passive"))
      (node (ref "R13") (pin "1") (pinfunction "1_1") (pintype "passive"))
    )
    (net (code "39") (name "Net-(LED3-Pad1)") (class "Default")
      (node (ref "LED3") (pin "1") (pinfunction "1_1") (pintype "passive"))
      (node (ref "R17") (pin "1") (pinfunction "1_1") (pintype "passive"))
    )
    (net (code "40") (name "Net-(LED4-Pad1)") (class "Default")
      (node (ref "LED4") (pin "1") (pinfunction "1_1") (pintype "passive"))
      (node (ref "R20") (pin "1") (pinfunction "1_1") (pintype "passive"))
    )
    (net (code "41") (name "Net-(P1-Pad1)") (class "Default")
      (node (ref "P1") (pin "1") (pintype "bidirectional"))
      (node (ref "R5") (pin "2") (pinfunction "2_2") (pintype "passive"))
    )
    (net (code "42") (name "Net-(Q1-B)") (class "Default")
      (node (ref "Q1") (pin "1") (pinfunction "B_1") (pintype "passive"))
      (node (ref "R1") (pin "2") (pinfunction "2_2") (pintype "passive"))
    )
    (net (code "43") (name "Net-(Q2-B)") (class "Default")
      (node (ref "Q2") (pin "1") (pinfunction "B_1") (pintype "passive"))
      (node (ref "R12") (pin "2") (pinfunction "2_2") (pintype "passive"))
    )
    (net (code "44") (name "Net-(Q2-C)") (class "Default")
      (node (ref "LED1") (pin "2") (pinfunction "2_2") (pintype "passive"))
      (node (ref "Q2") (pin "3") (pinfunction "C_3") (pintype "passive"))
    )
    (net (code "45") (name "Net-(Q3-B)") (class "Default")
      (node (ref "Q3") (pin "1") (pinfunction "B_1") (pintype "passive"))
      (node (ref "R16") (pin "2") (pinfunction "2_2") (pintype "passive"))
    )
    (net (code "46") (name "Net-(Q4-B)") (class "Default")
      (node (ref "Q4") (pin "1") (pinfunction "B_1") (pintype "passive"))
      (node (ref "R18") (pin "2") (pinfunction "2_2") (pintype "passive"))
    )
    (net (code "47") (name "Net-(RL1-Pad1)") (class "Default")
      (node (ref "RL1") (pin "1") (pinfunction "1_1") (pintype "passive"))
      (node (ref "SW1") (pin "1") (pinfunction "1_1") (pintype "passive"))
    )
    (net (code "48") (name "Net-(U1-GSM_ANT)") (class "Default")
      (node (ref "R5") (pin "1") (pinfunction "1_1") (pintype "passive"))
      (node (ref "U1") (pin "32") (pinfunction "GSM_ANT_32") (pintype "bidirectional"))
    )
    (net (code "49") (name "Net-(U1-UART1_RXD)") (class "Default")
      (node (ref "R2") (pin "2") (pinfunction "2_2") (pintype "passive"))
      (node (ref "R3") (pin "2") (pinfunction "2_2") (pintype "passive"))
      (node (ref "U1") (pin "2") (pinfunction "UART1_RXD_2") (pintype "input"))
    )
    (net (code "50") (name "Net-(U1-UART1_TXD)") (class "Default")
      (node (ref "R4") (pin "2") (pinfunction "2_2") (pintype "passive"))
      (node (ref "U1") (pin "1") (pinfunction "UART1_TXD_1") (pintype "output"))
    )
    (net (code "51") (name "Net-(U1-VRTC)") (class "Default")
      (node (ref "C1") (pin "1") (pinfunction "1_1") (pintype "passive"))
      (node (ref "U1") (pin "28") (pinfunction "VRTC_28") (pintype "power_in"))
    )
    (net (code "52") (name "Net-(U2-CLK)") (class "Default")
      (node (ref "R9") (pin "1") (pinfunction "1_1") (pintype "passive"))
      (node (ref "U2") (pin "3") (pinfunction "CLK_3") (pintype "passive"))
    )
    (net (code "53") (name "Net-(U2-DATA)") (class "Default")
      (node (ref "R8") (pin "1") (pinfunction "1_1") (pintype "passive"))
      (node (ref "U2") (pin "7") (pinfunction "DATA_7") (pintype "passive"))
    )
    (net (code "54") (name "Net-(U2-RST)") (class "Default")
      (node (ref "R10") (pin "1") (pinfunction "1_1") (pintype "passive"))
      (node (ref "U2") (pin "2") (pinfunction "RST_2") (pintype "passive"))
    )
    (net (code "55") (name "Net-(U3-IO32)") (class "Default")
      (node (ref "R17") (pin "2") (pinfunction "2_2") (pintype "passive"))
      (node (ref "U3") (pin "8") (pinfunction "IO32_8") (pintype "bidirectional"))
    )
    (net (code "56") (name "Net-(U3-IO33)") (class "Default")
      (node (ref "R20") (pin "2") (pinfunction "2_2") (pintype "passive"))
      (node (ref "U3") (pin "9") (pinfunction "IO33_9") (pintype "bidirectional"))
    )
    (net (code "57") (name "VCC") (class "Default")
      (node (ref "C13") (pin "1") (pinfunction "1_1") (pintype "passive"))
      (node (ref "C14") (pin "1") (pinfunction "1_1") (pintype "passive"))
      (node (ref "C3") (pin "1") (pinfunction "1_1") (pintype "passive"))
      (node (ref "C4") (pin "1") (pinfunction "1_1") (pintype "passive"))
      (node (ref "C5") (pin "1") (pinfunction "1_1") (pintype "passive"))
      (node (ref "C6") (pin "1") (pinfunction "1_1") (pintype "passive"))
      (node (ref "C7") (pin "1") (pinfunction "1_1") (pintype "passive"))
      (node (ref "C8") (pin "1") (pinfunction "1_1") (pintype "passive"))
      (node (ref "IC1") (pin "1") (pinfunction "VIN_1") (pintype "input"))
      (node (ref "IC2") (pin "1") (pinfunction "VIN_1") (pintype "input"))
      (node (ref "R11") (pin "2") (pinfunction "2_2") (pintype "passive"))
      (node (ref "R13") (pin "2") (pinfunction "2_2") (pintype "passive"))
      (node (ref "R6") (pin "2") (pinfunction "2_2") (pintype "passive"))
      (node (ref "R7") (pin "2") (pinfunction "2_2") (pintype "passive"))
      (node (ref "SW1") (pin "2") (pinfunction "2_2") (pintype "passive"))
      (node (ref "U1") (pin "34") (pinfunction "VBAT_34") (pintype "power_in"))
      (node (ref "U1") (pin "35") (pinfunction "VBAT_35") (pintype "power_in"))
    )
    (net (code "58") (name "unconnected-(IC1-NC-Pad4)") (class "Default")
      (node (ref "IC1") (pin "4") (pinfunction "NC_4") (pintype "passive"))
    )
    (net (code "59") (name "unconnected-(IC2-NC-Pad4)") (class "Default")
      (node (ref "IC2") (pin "4") (pinfunction "NC_4") (pintype "passive"))
    )
    (net (code "60") (name "unconnected-(IC3-DIO1-Pad6)") (class "Default")
      (node (ref "IC3") (pin "6") (pinfunction "DIO1_6") (pintype "passive"))
    )
    (net (code "61") (name "unconnected-(IC3-DIO2-Pad7)") (class "Default")
      (node (ref "IC3") (pin "7") (pinfunction "DIO2_7") (pintype "passive"))
    )
    (net (code "62") (name "unconnected-(IC3-DIO3-Pad8)") (class "Default")
      (node (ref "IC3") (pin "8") (pinfunction "DIO3_8") (pintype "passive"))
    )
    (net (code "63") (name "unconnected-(IC3-DIO4-Pad10)") (class "Default")
      (node (ref "IC3") (pin "10") (pinfunction "DIO4_10") (pintype "passive"))
    )
    (net (code "64") (name "unconnected-(IC3-DIO5-Pad11)") (class "Default")
      (node (ref "IC3") (pin "11") (pinfunction "DIO5_11") (pintype "passive"))
    )
    (net (code "65") (name "unconnected-(J2-P4-Pad4)") (class "Default")
      (node (ref "J2") (pin "4") (pinfunction "P4_4") (pintype "passive+no_connect"))
    )
    (net (code "66") (name "unconnected-(U1-ADC-Pad38)") (class "Default")
      (node (ref "U1") (pin "38") (pinfunction "ADC_38") (pintype "input+no_connect"))
    )
    (net (code "67") (name "unconnected-(U1-BT_ANT-Pad20)") (class "Default")
      (node (ref "U1") (pin "20") (pinfunction "BT_ANT_20") (pintype "bidirectional+no_connect"))
    )
    (net (code "68") (name "unconnected-(U1-MICN-Pad10)") (class "Default")
      (node (ref "U1") (pin "10") (pinfunction "MICN_10") (pintype "input+no_connect"))
    )
    (net (code "69") (name "unconnected-(U1-MICP-Pad9)") (class "Default")
      (node (ref "U1") (pin "9") (pinfunction "MICP_9") (pintype "input+no_connect"))
    )
    (net (code "70") (name "unconnected-(U1-RF_SYNC-Pad29)") (class "Default")
      (node (ref "U1") (pin "29") (pinfunction "RF_SYNC_29") (pintype "output+no_connect"))
    )
    (net (code "71") (name "unconnected-(U1-SIM_DET-Pad14)") (class "Default")
      (node (ref "U1") (pin "14") (pinfunction "SIM_DET_14") (pintype "input+no_connect"))
    )
    (net (code "72") (name "unconnected-(U1-SPKN-Pad12)") (class "Default")
      (node (ref "U1") (pin "12") (pinfunction "SPKN_12") (pintype "output+no_connect"))
    )
    (net (code "73") (name "unconnected-(U1-SPKP-Pad11)") (class "Default")
      (node (ref "U1") (pin "11") (pinfunction "SPKP_11") (pintype "output+no_connect"))
    )
    (net (code "74") (name "unconnected-(U1-UART1_CTS-Pad4)") (class "Default")
      (node (ref "U1") (pin "4") (pinfunction "UART1_CTS_4") (pintype "output+no_connect"))
    )
    (net (code "75") (name "unconnected-(U1-UART1_DCD-Pad5)") (class "Default")
      (node (ref "U1") (pin "5") (pinfunction "UART1_DCD_5") (pintype "output+no_connect"))
    )
    (net (code "76") (name "unconnected-(U1-UART1_DTR-Pad6)") (class "Default")
      (node (ref "U1") (pin "6") (pinfunction "UART1_DTR_6") (pintype "input+no_connect"))
    )
    (net (code "77") (name "unconnected-(U1-UART1_RI-Pad7)") (class "Default")
      (node (ref "U1") (pin "7") (pinfunction "UART1_RI_7") (pintype "output+no_connect"))
    )
    (net (code "78") (name "unconnected-(U1-UART1_RTS-Pad3)") (class "Default")
      (node (ref "U1") (pin "3") (pinfunction "UART1_RTS_3") (pintype "input+no_connect"))
    )
    (net (code "79") (name "unconnected-(U1-UART2_RXD-Pad23)") (class "Default")
      (node (ref "U1") (pin "23") (pinfunction "UART2_RXD_23") (pintype "input+no_connect"))
    )
    (net (code "80") (name "unconnected-(U1-UART2_TXD-Pad22)") (class "Default")
      (node (ref "U1") (pin "22") (pinfunction "UART2_TXD_22") (pintype "output"))
    )
    (net (code "81") (name "unconnected-(U1-USB_DN-Pad26)") (class "Default")
      (node (ref "U1") (pin "26") (pinfunction "USB_DN_26") (pintype "bidirectional+no_connect"))
    )
    (net (code "82") (name "unconnected-(U1-USB_DP-Pad25)") (class "Default")
      (node (ref "U1") (pin "25") (pinfunction "USB_DP_25") (pintype "bidirectional+no_connect"))
    )
    (net (code "83") (name "unconnected-(U1-USB_VBUS-Pad24)") (class "Default")
      (node (ref "U1") (pin "24") (pinfunction "USB_VBUS_24") (pintype "input+no_connect"))
    )
    (net (code "84") (name "unconnected-(U1-VDD_EXT-Pad40)") (class "Default")
      (node (ref "U1") (pin "40") (pinfunction "VDD_EXT_40") (pintype "power_in+no_connect"))
    )
    (net (code "85") (name "unconnected-(U2-GND-Pad8)") (class "Default")
      (node (ref "U2") (pin "8") (pinfunction "GND_8") (pintype "passive"))
    )
    (net (code "86") (name "unconnected-(U2-PRENSENCE-Pad4)") (class "Default")
      (node (ref "U2") (pin "4") (pinfunction "PRENSENCE_4") (pintype "passive"))
    )
    (net (code "87") (name "unconnected-(U2-VPP-Pad6)") (class "Default")
      (node (ref "U2") (pin "6") (pinfunction "VPP_6") (pintype "passive"))
    )
    (net (code "88") (name "unconnected-(U3-IO12-Pad14)") (class "Default")
      (node (ref "U3") (pin "14") (pinfunction "IO12_14") (pintype "bidirectional"))
    )
    (net (code "89") (name "unconnected-(U3-IO13-Pad16)") (class "Default")
      (node (ref "U3") (pin "16") (pinfunction "IO13_16") (pintype "bidirectional"))
    )
    (net (code "90") (name "unconnected-(U3-IO14-Pad13)") (class "Default")
      (node (ref "U3") (pin "13") (pinfunction "IO14_13") (pintype "bidirectional"))
    )
    (net (code "91") (name "unconnected-(U3-IO15-Pad23)") (class "Default")
      (node (ref "U3") (pin "23") (pinfunction "IO15_23") (pintype "bidirectional"))
    )
    (net (code "92") (name "unconnected-(U3-IO26-Pad11)") (class "Default")
      (node (ref "U3") (pin "11") (pinfunction "IO26_11") (pintype "bidirectional"))
    )
    (net (code "93") (name "unconnected-(U3-IO27-Pad12)") (class "Default")
      (node (ref "U3") (pin "12") (pinfunction "IO27_12") (pintype "bidirectional"))
    )
    (net (code "94") (name "unconnected-(U3-IO34-Pad6)") (class "Default")
      (node (ref "U3") (pin "6") (pinfunction "IO34_6") (pintype "input"))
    )
    (net (code "95") (name "unconnected-(U3-IO35-Pad7)") (class "Default")
      (node (ref "U3") (pin "7") (pinfunction "IO35_7") (pintype "input"))
    )
    (net (code "96") (name "unconnected-(U3-SCK{slash}CLK-Pad20)") (class "Default")
      (node (ref "U3") (pin "20") (pinfunction "SCK/CLK_20") (pintype "bidirectional"))
    )
    (net (code "97") (name "unconnected-(U3-SCS{slash}CMD-Pad19)") (class "Default")
      (node (ref "U3") (pin "19") (pinfunction "SCS/CMD_19") (pintype "bidirectional"))
    )
    (net (code "98") (name "unconnected-(U3-SENSOR_VN-Pad5)") (class "Default")
      (node (ref "U3") (pin "5") (pinfunction "SENSOR_VN_5") (pintype "input"))
    )
    (net (code "99") (name "unconnected-(U3-SENSOR_VP-Pad4)") (class "Default")
      (node (ref "U3") (pin "4") (pinfunction "SENSOR_VP_4") (pintype "input"))
    )
    (net (code "100") (name "unconnected-(U3-SHD{slash}SD2-Pad17)") (class "Default")
      (node (ref "U3") (pin "17") (pinfunction "SHD/SD2_17") (pintype "bidirectional"))
    )
    (net (code "101") (name "unconnected-(U3-SWP{slash}SD3-Pad18)") (class "Default")
      (node (ref "U3") (pin "18") (pinfunction "SWP/SD3_18") (pintype "bidirectional"))
    )
    (net (code "102") (name "unconnected-(U4-R232-Pad15)") (class "Default")
      (node (ref "U4") (pin "15") (pinfunction "R232_15") (pintype "bidirectional"))
    )
    (net (code "103") (name "unconnected-(U4-~{CTS}-Pad9)") (class "Default")
      (node (ref "U4") (pin "9") (pinfunction "~{CTS}_9") (pintype "bidirectional"))
    )
    (net (code "104") (name "unconnected-(U4-~{DCD}-Pad12)") (class "Default")
      (node (ref "U4") (pin "12") (pinfunction "~{DCD}_12") (pintype "bidirectional"))
    )
    (net (code "105") (name "unconnected-(U4-~{DSR}-Pad10)") (class "Default")
      (node (ref "U4") (pin "10") (pinfunction "~{DSR}_10") (pintype "bidirectional"))
    )
    (net (code "106") (name "unconnected-(U4-~{RI}-Pad11)") (class "Default")
      (node (ref "U4") (pin "11") (pinfunction "~{RI}_11") (pintype "bidirectional"))
    )
  )
)
